# hackeeg-connector-24.net
KiCad netlist of a schematic drawn in EAGLE
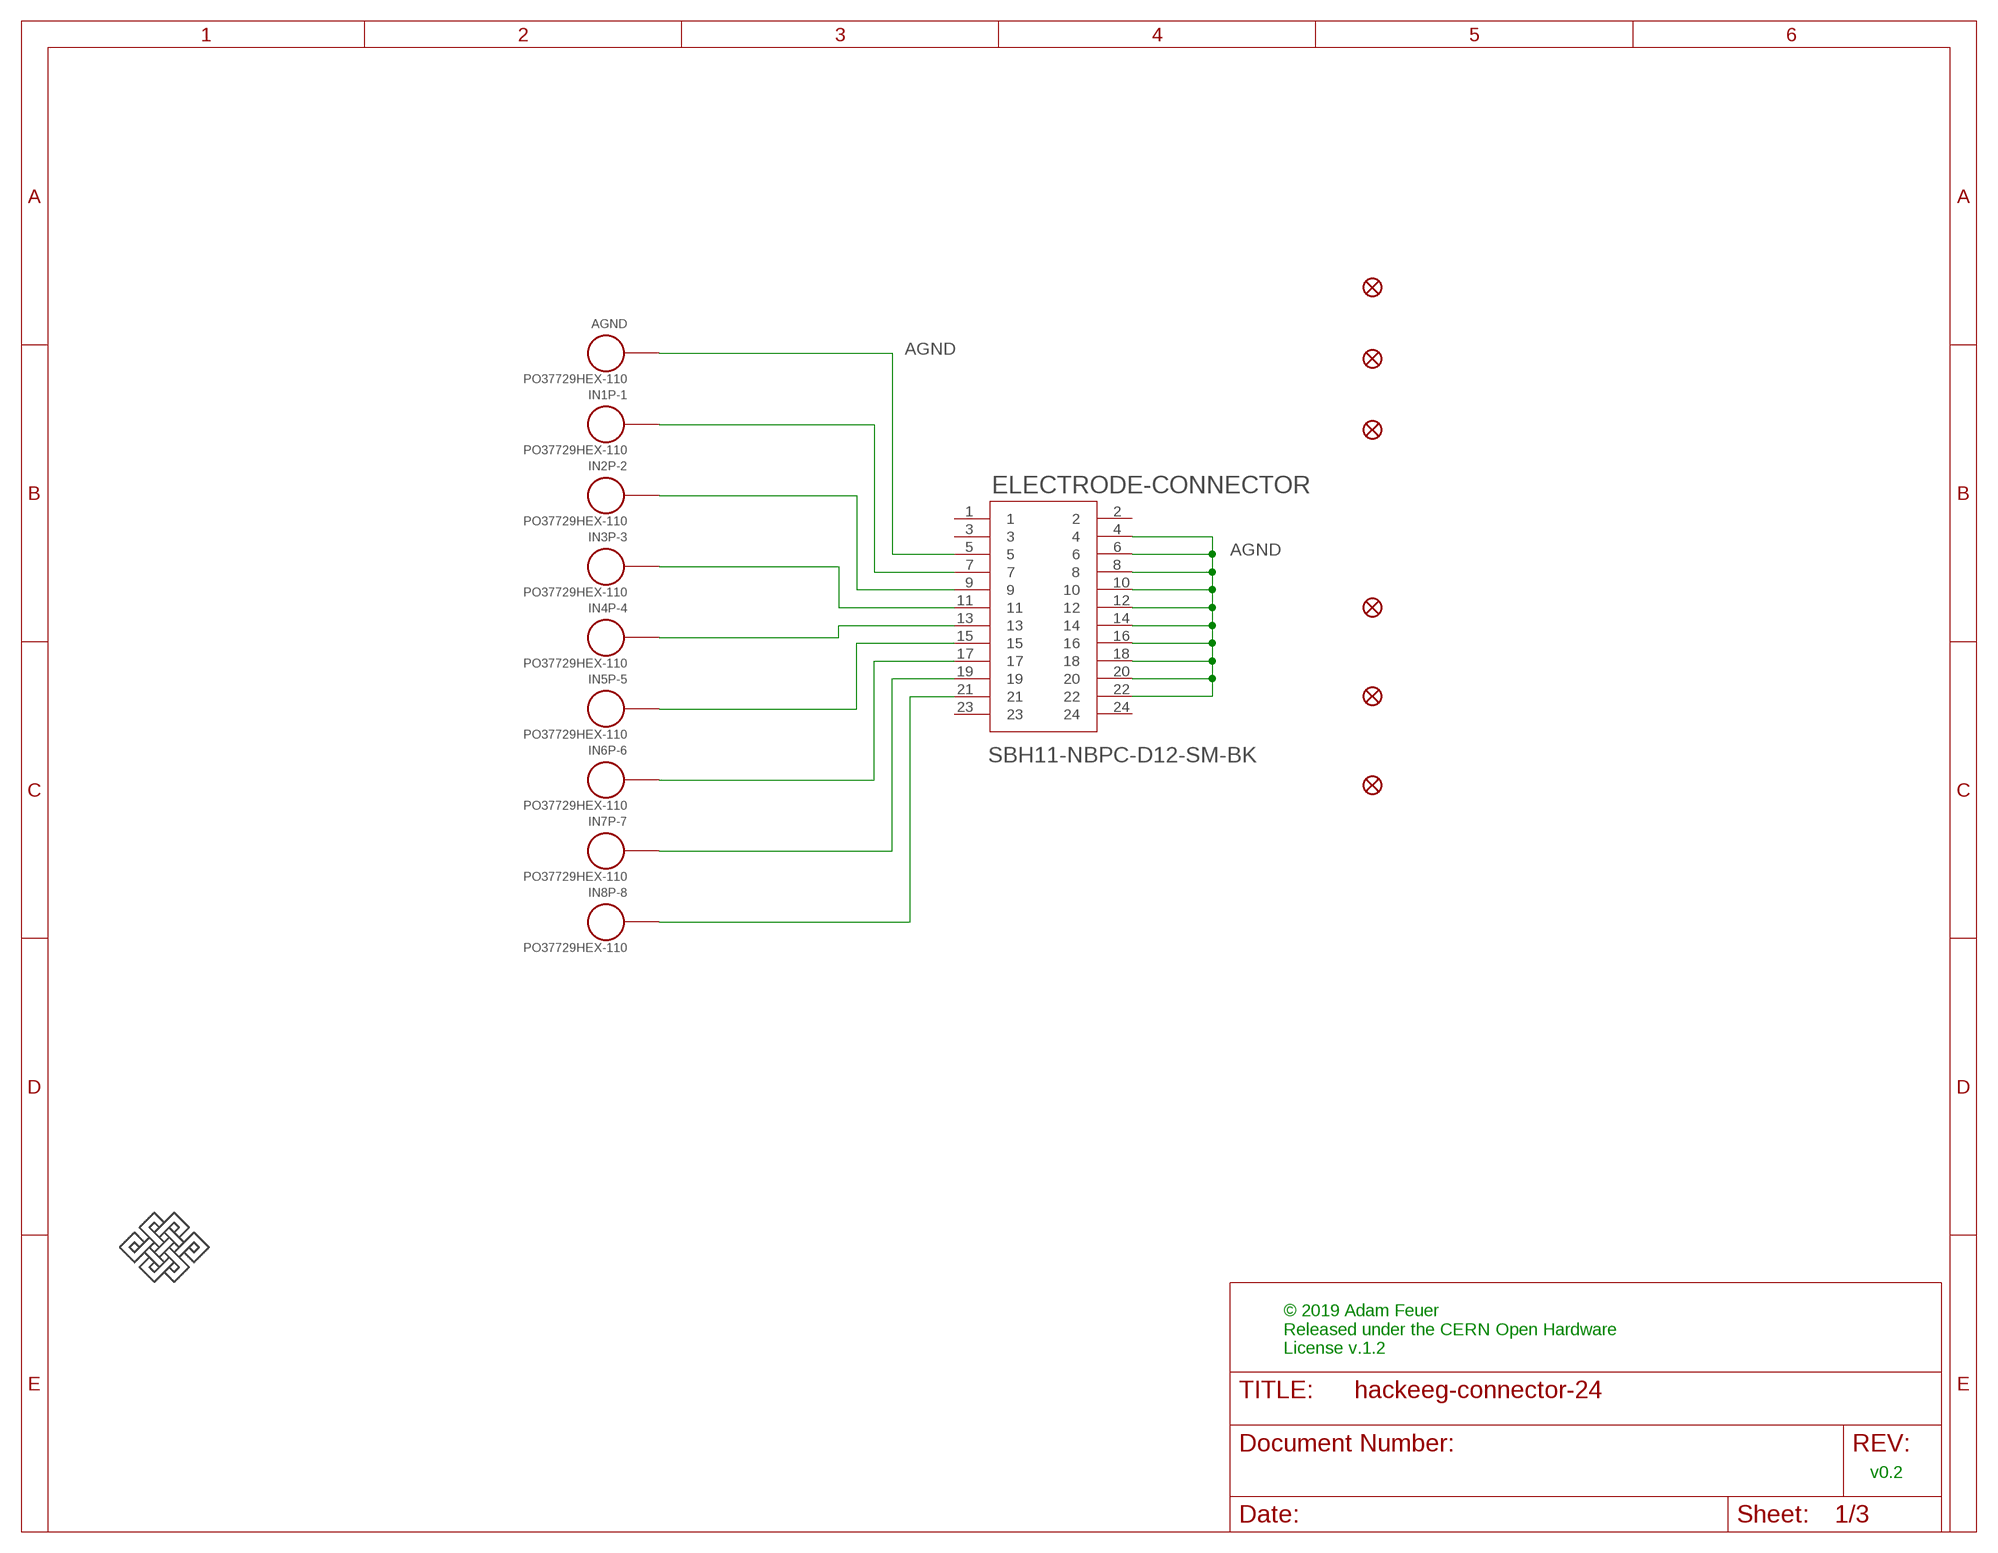
[diagram p0: schematic, sheet 1]
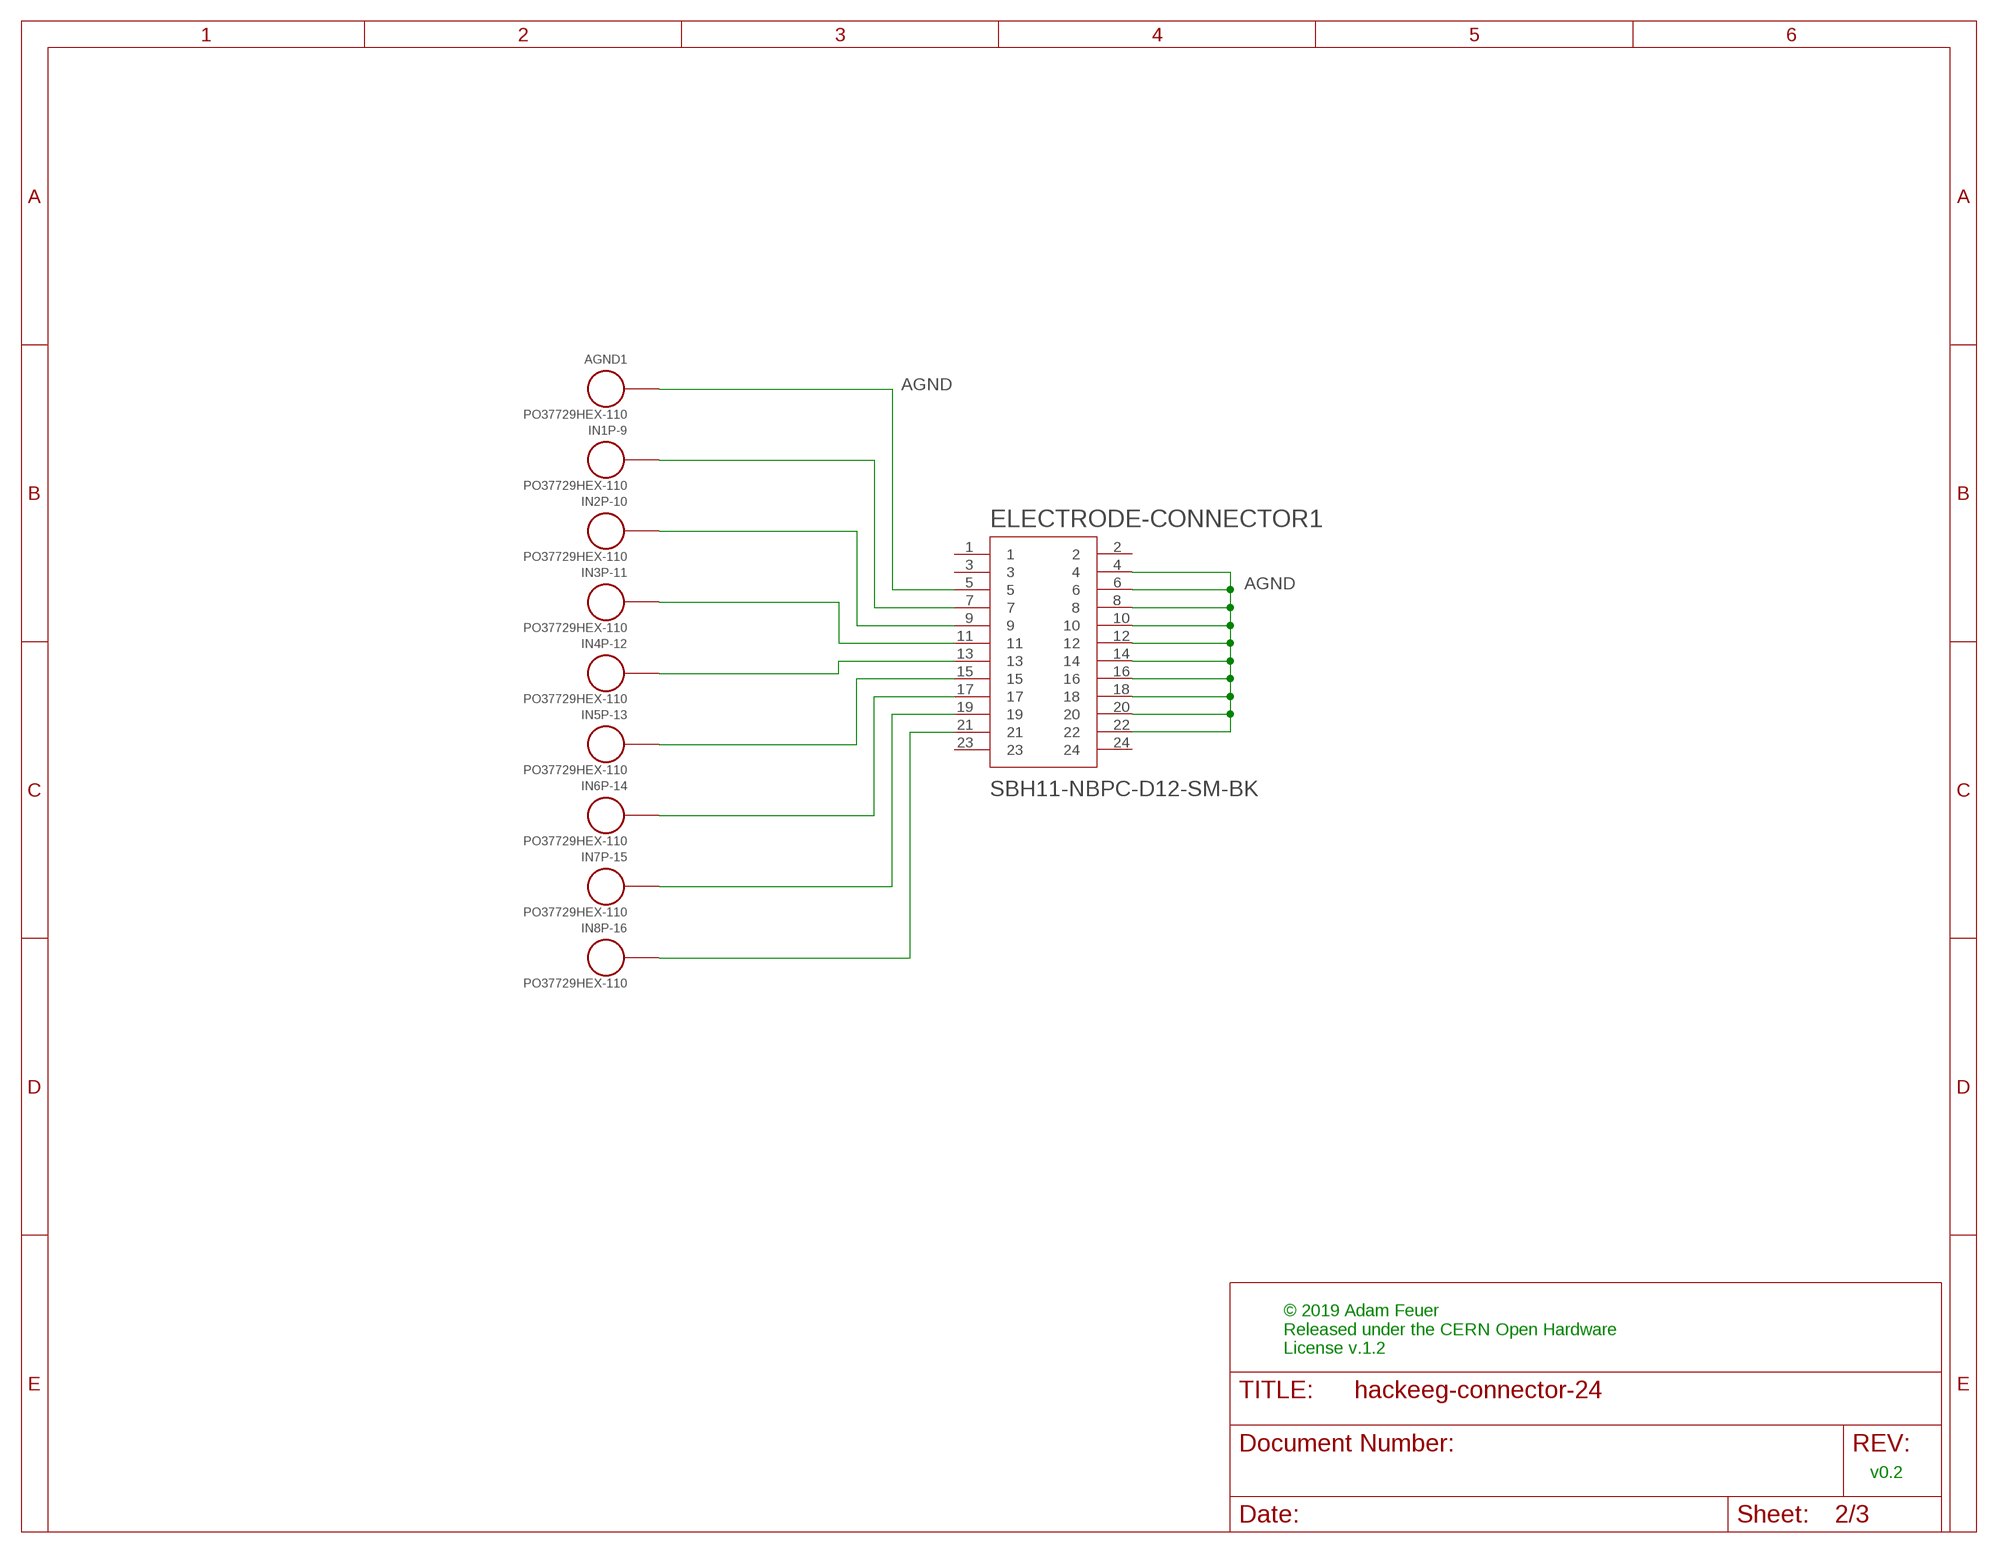
[diagram p1: schematic, sheet 2]
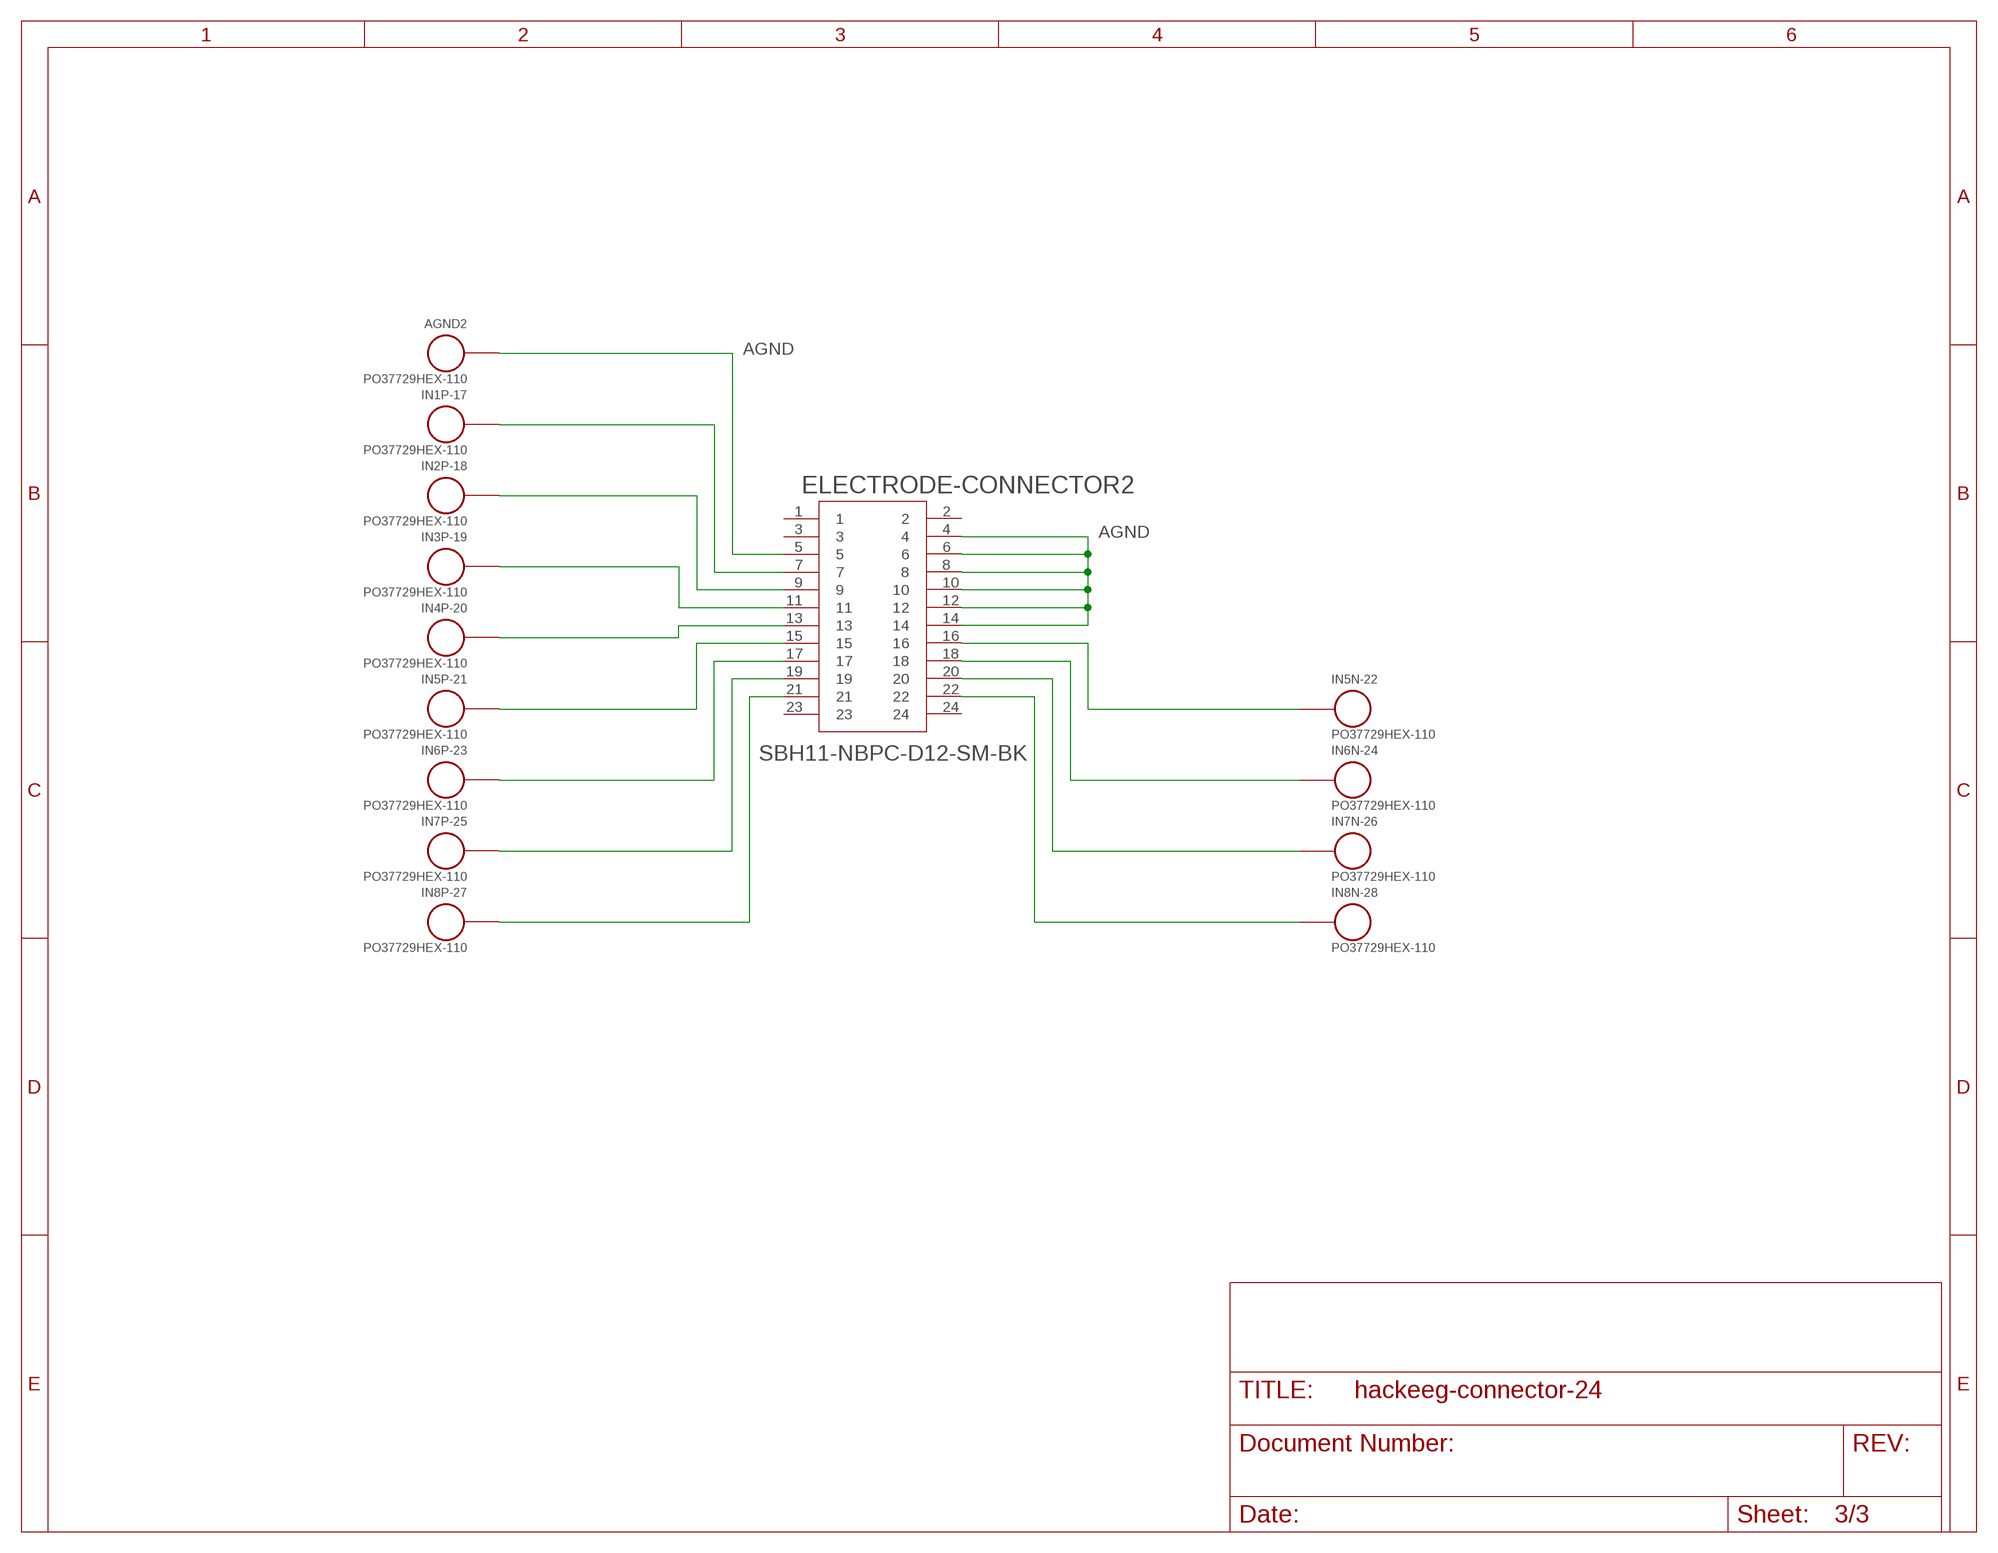
[diagram p2: schematic, sheet 3]

(export (version "E")
  (design (tool "Eeschema 10.0.6"))
  (components
    (comp (ref "AGND2")
      (value "PO37729HEX-110")
      (footprint "eagle-import:HEX-110")
      (libsource (lib "eagle-import") (part "PO37729HEX-110"))
    )
    (comp (ref "ELECTRODE-CONNECTOR2")
      (value "SBH11-NBPC-D12-SM-BK")
      (footprint "eagle-import:SULLINS_SBH11-NBPC-D12-SM-BK")
      (fields (field (name "MF") "Sullins Connector"))
      (libsource (lib "eagle-import") (part "SBH11-NBPC-D12-SM-BK"))
    )
    (comp (ref "IN1P-17")
      (value "PO37729HEX-110")
      (footprint "eagle-import:HEX-110")
      (libsource (lib "eagle-import") (part "PO37729HEX-110"))
    )
    (comp (ref "IN2P-18")
      (value "PO37729HEX-110")
      (footprint "eagle-import:HEX-110")
      (libsource (lib "eagle-import") (part "PO37729HEX-110"))
    )
    (comp (ref "IN3P-19")
      (value "PO37729HEX-110")
      (footprint "eagle-import:HEX-110")
      (libsource (lib "eagle-import") (part "PO37729HEX-110"))
    )
    (comp (ref "IN4P-20")
      (value "PO37729HEX-110")
      (footprint "eagle-import:HEX-110")
      (libsource (lib "eagle-import") (part "PO37729HEX-110"))
    )
    (comp (ref "IN5N-22")
      (value "PO37729HEX-110")
      (footprint "eagle-import:HEX-110")
      (libsource (lib "eagle-import") (part "PO37729HEX-110"))
    )
    (comp (ref "IN5P-21")
      (value "PO37729HEX-110")
      (footprint "eagle-import:HEX-110")
      (libsource (lib "eagle-import") (part "PO37729HEX-110"))
    )
    (comp (ref "IN6N-24")
      (value "PO37729HEX-110")
      (footprint "eagle-import:HEX-110")
      (libsource (lib "eagle-import") (part "PO37729HEX-110"))
    )
    (comp (ref "IN6P-23")
      (value "PO37729HEX-110")
      (footprint "eagle-import:HEX-110")
      (libsource (lib "eagle-import") (part "PO37729HEX-110"))
    )
    (comp (ref "IN7N-26")
      (value "PO37729HEX-110")
      (footprint "eagle-import:HEX-110")
      (libsource (lib "eagle-import") (part "PO37729HEX-110"))
    )
    (comp (ref "IN7P-25")
      (value "PO37729HEX-110")
      (footprint "eagle-import:HEX-110")
      (libsource (lib "eagle-import") (part "PO37729HEX-110"))
    )
    (comp (ref "IN8N-28")
      (value "PO37729HEX-110")
      (footprint "eagle-import:HEX-110")
      (libsource (lib "eagle-import") (part "PO37729HEX-110"))
    )
    (comp (ref "IN8P-27")
      (value "PO37729HEX-110")
      (footprint "eagle-import:HEX-110")
      (libsource (lib "eagle-import") (part "PO37729HEX-110"))
    )
    (comp (ref "AGND")
      (value "PO37729HEX-110")
      (footprint "eagle-import:HEX-110")
      (libsource (lib "eagle-import") (part "PO37729HEX-110"))
    )
    (comp (ref "ELECTRODE-CONNECTOR")
      (value "SBH11-NBPC-D12-SM-BK")
      (footprint "eagle-import:SULLINS_SBH11-NBPC-D12-SM-BK")
      (fields (field (name "MF") "Sullins Connector"))
      (libsource (lib "eagle-import") (part "SBH11-NBPC-D12-SM-BK"))
    )
    (comp (ref "FD1")
      (value "FIDUCIAL1X2")
      (footprint "eagle-import:FIDUCIAL-1X2")
      (libsource (lib "eagle-import") (part "FIDUCIAL1X2"))
    )
    (comp (ref "FD2")
      (value "FIDUCIAL1X2")
      (footprint "eagle-import:FIDUCIAL-1X2")
      (libsource (lib "eagle-import") (part "FIDUCIAL1X2"))
    )
    (comp (ref "FD3")
      (value "FIDUCIAL1X2")
      (footprint "eagle-import:FIDUCIAL-1X2")
      (libsource (lib "eagle-import") (part "FIDUCIAL1X2"))
    )
    (comp (ref "FD4")
      (value "FIDUCIAL1X2")
      (footprint "eagle-import:FIDUCIAL-1X2")
      (libsource (lib "eagle-import") (part "FIDUCIAL1X2"))
    )
    (comp (ref "FD5")
      (value "FIDUCIAL1X2")
      (footprint "eagle-import:FIDUCIAL-1X2")
      (libsource (lib "eagle-import") (part "FIDUCIAL1X2"))
    )
    (comp (ref "FD6")
      (value "FIDUCIAL1X2")
      (footprint "eagle-import:FIDUCIAL-1X2")
      (libsource (lib "eagle-import") (part "FIDUCIAL1X2"))
    )
    (comp (ref "IN1P-1")
      (value "PO37729HEX-110")
      (footprint "eagle-import:HEX-110")
      (libsource (lib "eagle-import") (part "PO37729HEX-110"))
    )
    (comp (ref "IN2P-2")
      (value "PO37729HEX-110")
      (footprint "eagle-import:HEX-110")
      (libsource (lib "eagle-import") (part "PO37729HEX-110"))
    )
    (comp (ref "IN3P-3")
      (value "PO37729HEX-110")
      (footprint "eagle-import:HEX-110")
      (libsource (lib "eagle-import") (part "PO37729HEX-110"))
    )
    (comp (ref "IN4P-4")
      (value "PO37729HEX-110")
      (footprint "eagle-import:HEX-110")
      (libsource (lib "eagle-import") (part "PO37729HEX-110"))
    )
    (comp (ref "IN5P-5")
      (value "PO37729HEX-110")
      (footprint "eagle-import:HEX-110")
      (libsource (lib "eagle-import") (part "PO37729HEX-110"))
    )
    (comp (ref "IN6P-6")
      (value "PO37729HEX-110")
      (footprint "eagle-import:HEX-110")
      (libsource (lib "eagle-import") (part "PO37729HEX-110"))
    )
    (comp (ref "IN7P-7")
      (value "PO37729HEX-110")
      (footprint "eagle-import:HEX-110")
      (libsource (lib "eagle-import") (part "PO37729HEX-110"))
    )
    (comp (ref "IN8P-8")
      (value "PO37729HEX-110")
      (footprint "eagle-import:HEX-110")
      (libsource (lib "eagle-import") (part "PO37729HEX-110"))
    )
    (comp (ref "U$1")
      (value "ENDLESSKNOTENDLESSKNOT-MEDIUM")
      (footprint "eagle-import:ENDLESSKNOT-MEDIUM")
      (libsource (lib "eagle-import") (part "ENDLESSKNOTENDLESSKNOT-MEDIUM"))
    )
    (comp (ref "AGND1")
      (value "PO37729HEX-110")
      (footprint "eagle-import:HEX-110")
      (libsource (lib "eagle-import") (part "PO37729HEX-110"))
    )
    (comp (ref "ELECTRODE-CONNECTOR1")
      (value "SBH11-NBPC-D12-SM-BK")
      (footprint "eagle-import:SULLINS_SBH11-NBPC-D12-SM-BK")
      (fields (field (name "MF") "Sullins Connector"))
      (libsource (lib "eagle-import") (part "SBH11-NBPC-D12-SM-BK"))
    )
    (comp (ref "IN1P-9")
      (value "PO37729HEX-110")
      (footprint "eagle-import:HEX-110")
      (libsource (lib "eagle-import") (part "PO37729HEX-110"))
    )
    (comp (ref "IN2P-10")
      (value "PO37729HEX-110")
      (footprint "eagle-import:HEX-110")
      (libsource (lib "eagle-import") (part "PO37729HEX-110"))
    )
    (comp (ref "IN3P-11")
      (value "PO37729HEX-110")
      (footprint "eagle-import:HEX-110")
      (libsource (lib "eagle-import") (part "PO37729HEX-110"))
    )
    (comp (ref "IN4P-12")
      (value "PO37729HEX-110")
      (footprint "eagle-import:HEX-110")
      (libsource (lib "eagle-import") (part "PO37729HEX-110"))
    )
    (comp (ref "IN5P-13")
      (value "PO37729HEX-110")
      (footprint "eagle-import:HEX-110")
      (libsource (lib "eagle-import") (part "PO37729HEX-110"))
    )
    (comp (ref "IN6P-14")
      (value "PO37729HEX-110")
      (footprint "eagle-import:HEX-110")
      (libsource (lib "eagle-import") (part "PO37729HEX-110"))
    )
    (comp (ref "IN7P-15")
      (value "PO37729HEX-110")
      (footprint "eagle-import:HEX-110")
      (libsource (lib "eagle-import") (part "PO37729HEX-110"))
    )
    (comp (ref "IN8P-16")
      (value "PO37729HEX-110")
      (footprint "eagle-import:HEX-110")
      (libsource (lib "eagle-import") (part "PO37729HEX-110"))
    )
  )
  (nets
    (net (code "1") (name "AGND") (class "Default")
      (node (ref "AGND") (pin "SIGNAL") (pinfunction "SIGNAL_SIGNAL") (pintype "bidirectional"))
      (node (ref "AGND1") (pin "SIGNAL") (pinfunction "SIGNAL_SIGNAL") (pintype "bidirectional"))
      (node (ref "AGND2") (pin "SIGNAL") (pinfunction "SIGNAL_SIGNAL") (pintype "bidirectional"))
      (node (ref "ELECTRODE-CONNECTOR") (pin "10") (pinfunction "10_10") (pintype "passive"))
      (node (ref "ELECTRODE-CONNECTOR") (pin "12") (pinfunction "12_12") (pintype "passive"))
      (node (ref "ELECTRODE-CONNECTOR") (pin "14") (pinfunction "14_14") (pintype "passive"))
      (node (ref "ELECTRODE-CONNECTOR") (pin "16") (pinfunction "16_16") (pintype "passive"))
      (node (ref "ELECTRODE-CONNECTOR") (pin "18") (pinfunction "18_18") (pintype "passive"))
      (node (ref "ELECTRODE-CONNECTOR") (pin "20") (pinfunction "20_20") (pintype "passive"))
      (node (ref "ELECTRODE-CONNECTOR") (pin "22") (pinfunction "22_22") (pintype "passive"))
      (node (ref "ELECTRODE-CONNECTOR") (pin "4") (pinfunction "4_4") (pintype "passive"))
      (node (ref "ELECTRODE-CONNECTOR") (pin "5") (pinfunction "5_5") (pintype "passive"))
      (node (ref "ELECTRODE-CONNECTOR") (pin "6") (pinfunction "6_6") (pintype "passive"))
      (node (ref "ELECTRODE-CONNECTOR") (pin "8") (pinfunction "8_8") (pintype "passive"))
      (node (ref "ELECTRODE-CONNECTOR1") (pin "10") (pinfunction "10_10") (pintype "passive"))
      (node (ref "ELECTRODE-CONNECTOR1") (pin "12") (pinfunction "12_12") (pintype "passive"))
      (node (ref "ELECTRODE-CONNECTOR1") (pin "14") (pinfunction "14_14") (pintype "passive"))
      (node (ref "ELECTRODE-CONNECTOR1") (pin "16") (pinfunction "16_16") (pintype "passive"))
      (node (ref "ELECTRODE-CONNECTOR1") (pin "18") (pinfunction "18_18") (pintype "passive"))
      (node (ref "ELECTRODE-CONNECTOR1") (pin "20") (pinfunction "20_20") (pintype "passive"))
      (node (ref "ELECTRODE-CONNECTOR1") (pin "22") (pinfunction "22_22") (pintype "passive"))
      (node (ref "ELECTRODE-CONNECTOR1") (pin "4") (pinfunction "4_4") (pintype "passive"))
      (node (ref "ELECTRODE-CONNECTOR1") (pin "5") (pinfunction "5_5") (pintype "passive"))
      (node (ref "ELECTRODE-CONNECTOR1") (pin "6") (pinfunction "6_6") (pintype "passive"))
      (node (ref "ELECTRODE-CONNECTOR1") (pin "8") (pinfunction "8_8") (pintype "passive"))
      (node (ref "ELECTRODE-CONNECTOR2") (pin "10") (pinfunction "10_10") (pintype "passive"))
      (node (ref "ELECTRODE-CONNECTOR2") (pin "12") (pinfunction "12_12") (pintype "passive"))
      (node (ref "ELECTRODE-CONNECTOR2") (pin "14") (pinfunction "14_14") (pintype "passive"))
      (node (ref "ELECTRODE-CONNECTOR2") (pin "4") (pinfunction "4_4") (pintype "passive"))
      (node (ref "ELECTRODE-CONNECTOR2") (pin "5") (pinfunction "5_5") (pintype "passive"))
      (node (ref "ELECTRODE-CONNECTOR2") (pin "6") (pinfunction "6_6") (pintype "passive"))
      (node (ref "ELECTRODE-CONNECTOR2") (pin "8") (pinfunction "8_8") (pintype "passive"))
    )
    (net (code "2") (name "Net-(ELECTRODE-CONNECTOR-Pad7)") (class "Default")
      (node (ref "ELECTRODE-CONNECTOR") (pin "7") (pinfunction "7_7") (pintype "passive"))
      (node (ref "IN1P-1") (pin "SIGNAL") (pinfunction "SIGNAL_SIGNAL") (pintype "bidirectional"))
    )
    (net (code "3") (name "Net-(ELECTRODE-CONNECTOR-Pad9)") (class "Default")
      (node (ref "ELECTRODE-CONNECTOR") (pin "9") (pinfunction "9_9") (pintype "passive"))
      (node (ref "IN2P-2") (pin "SIGNAL") (pinfunction "SIGNAL_SIGNAL") (pintype "bidirectional"))
    )
    (net (code "4") (name "Net-(ELECTRODE-CONNECTOR-Pad11)") (class "Default")
      (node (ref "ELECTRODE-CONNECTOR") (pin "11") (pinfunction "11_11") (pintype "passive"))
      (node (ref "IN3P-3") (pin "SIGNAL") (pinfunction "SIGNAL_SIGNAL") (pintype "bidirectional"))
    )
    (net (code "5") (name "Net-(ELECTRODE-CONNECTOR-Pad13)") (class "Default")
      (node (ref "ELECTRODE-CONNECTOR") (pin "13") (pinfunction "13_13") (pintype "passive"))
      (node (ref "IN4P-4") (pin "SIGNAL") (pinfunction "SIGNAL_SIGNAL") (pintype "bidirectional"))
    )
    (net (code "6") (name "Net-(ELECTRODE-CONNECTOR-Pad15)") (class "Default")
      (node (ref "ELECTRODE-CONNECTOR") (pin "15") (pinfunction "15_15") (pintype "passive"))
      (node (ref "IN5P-5") (pin "SIGNAL") (pinfunction "SIGNAL_SIGNAL") (pintype "bidirectional"))
    )
    (net (code "7") (name "Net-(ELECTRODE-CONNECTOR-Pad17)") (class "Default")
      (node (ref "ELECTRODE-CONNECTOR") (pin "17") (pinfunction "17_17") (pintype "passive"))
      (node (ref "IN6P-6") (pin "SIGNAL") (pinfunction "SIGNAL_SIGNAL") (pintype "bidirectional"))
    )
    (net (code "8") (name "Net-(ELECTRODE-CONNECTOR-Pad19)") (class "Default")
      (node (ref "ELECTRODE-CONNECTOR") (pin "19") (pinfunction "19_19") (pintype "passive"))
      (node (ref "IN7P-7") (pin "SIGNAL") (pinfunction "SIGNAL_SIGNAL") (pintype "bidirectional"))
    )
    (net (code "9") (name "Net-(ELECTRODE-CONNECTOR-Pad21)") (class "Default")
      (node (ref "ELECTRODE-CONNECTOR") (pin "21") (pinfunction "21_21") (pintype "passive"))
      (node (ref "IN8P-8") (pin "SIGNAL") (pinfunction "SIGNAL_SIGNAL") (pintype "bidirectional"))
    )
    (net (code "10") (name "Net-(ELECTRODE-CONNECTOR1-Pad7)") (class "Default")
      (node (ref "ELECTRODE-CONNECTOR1") (pin "7") (pinfunction "7_7") (pintype "passive"))
      (node (ref "IN1P-9") (pin "SIGNAL") (pinfunction "SIGNAL_SIGNAL") (pintype "bidirectional"))
    )
    (net (code "11") (name "Net-(ELECTRODE-CONNECTOR1-Pad9)") (class "Default")
      (node (ref "ELECTRODE-CONNECTOR1") (pin "9") (pinfunction "9_9") (pintype "passive"))
      (node (ref "IN2P-10") (pin "SIGNAL") (pinfunction "SIGNAL_SIGNAL") (pintype "bidirectional"))
    )
    (net (code "12") (name "Net-(ELECTRODE-CONNECTOR1-Pad11)") (class "Default")
      (node (ref "ELECTRODE-CONNECTOR1") (pin "11") (pinfunction "11_11") (pintype "passive"))
      (node (ref "IN3P-11") (pin "SIGNAL") (pinfunction "SIGNAL_SIGNAL") (pintype "bidirectional"))
    )
    (net (code "13") (name "Net-(ELECTRODE-CONNECTOR1-Pad13)") (class "Default")
      (node (ref "ELECTRODE-CONNECTOR1") (pin "13") (pinfunction "13_13") (pintype "passive"))
      (node (ref "IN4P-12") (pin "SIGNAL") (pinfunction "SIGNAL_SIGNAL") (pintype "bidirectional"))
    )
    (net (code "14") (name "Net-(ELECTRODE-CONNECTOR1-Pad15)") (class "Default")
      (node (ref "ELECTRODE-CONNECTOR1") (pin "15") (pinfunction "15_15") (pintype "passive"))
      (node (ref "IN5P-13") (pin "SIGNAL") (pinfunction "SIGNAL_SIGNAL") (pintype "bidirectional"))
    )
    (net (code "15") (name "Net-(ELECTRODE-CONNECTOR1-Pad17)") (class "Default")
      (node (ref "ELECTRODE-CONNECTOR1") (pin "17") (pinfunction "17_17") (pintype "passive"))
      (node (ref "IN6P-14") (pin "SIGNAL") (pinfunction "SIGNAL_SIGNAL") (pintype "bidirectional"))
    )
    (net (code "16") (name "Net-(ELECTRODE-CONNECTOR1-Pad19)") (class "Default")
      (node (ref "ELECTRODE-CONNECTOR1") (pin "19") (pinfunction "19_19") (pintype "passive"))
      (node (ref "IN7P-15") (pin "SIGNAL") (pinfunction "SIGNAL_SIGNAL") (pintype "bidirectional"))
    )
    (net (code "17") (name "Net-(ELECTRODE-CONNECTOR1-Pad21)") (class "Default")
      (node (ref "ELECTRODE-CONNECTOR1") (pin "21") (pinfunction "21_21") (pintype "passive"))
      (node (ref "IN8P-16") (pin "SIGNAL") (pinfunction "SIGNAL_SIGNAL") (pintype "bidirectional"))
    )
    (net (code "18") (name "Net-(ELECTRODE-CONNECTOR2-Pad7)") (class "Default")
      (node (ref "ELECTRODE-CONNECTOR2") (pin "7") (pinfunction "7_7") (pintype "passive"))
      (node (ref "IN1P-17") (pin "SIGNAL") (pinfunction "SIGNAL_SIGNAL") (pintype "bidirectional"))
    )
    (net (code "19") (name "Net-(ELECTRODE-CONNECTOR2-Pad9)") (class "Default")
      (node (ref "ELECTRODE-CONNECTOR2") (pin "9") (pinfunction "9_9") (pintype "passive"))
      (node (ref "IN2P-18") (pin "SIGNAL") (pinfunction "SIGNAL_SIGNAL") (pintype "bidirectional"))
    )
    (net (code "20") (name "Net-(ELECTRODE-CONNECTOR2-Pad11)") (class "Default")
      (node (ref "ELECTRODE-CONNECTOR2") (pin "11") (pinfunction "11_11") (pintype "passive"))
      (node (ref "IN3P-19") (pin "SIGNAL") (pinfunction "SIGNAL_SIGNAL") (pintype "bidirectional"))
    )
    (net (code "21") (name "Net-(ELECTRODE-CONNECTOR2-Pad13)") (class "Default")
      (node (ref "ELECTRODE-CONNECTOR2") (pin "13") (pinfunction "13_13") (pintype "passive"))
      (node (ref "IN4P-20") (pin "SIGNAL") (pinfunction "SIGNAL_SIGNAL") (pintype "bidirectional"))
    )
    (net (code "22") (name "Net-(ELECTRODE-CONNECTOR2-Pad15)") (class "Default")
      (node (ref "ELECTRODE-CONNECTOR2") (pin "15") (pinfunction "15_15") (pintype "passive"))
      (node (ref "IN5P-21") (pin "SIGNAL") (pinfunction "SIGNAL_SIGNAL") (pintype "bidirectional"))
    )
    (net (code "23") (name "Net-(ELECTRODE-CONNECTOR2-Pad16)") (class "Default")
      (node (ref "ELECTRODE-CONNECTOR2") (pin "16") (pinfunction "16_16") (pintype "passive"))
      (node (ref "IN5N-22") (pin "SIGNAL") (pinfunction "SIGNAL_SIGNAL") (pintype "bidirectional"))
    )
    (net (code "24") (name "Net-(ELECTRODE-CONNECTOR2-Pad17)") (class "Default")
      (node (ref "ELECTRODE-CONNECTOR2") (pin "17") (pinfunction "17_17") (pintype "passive"))
      (node (ref "IN6P-23") (pin "SIGNAL") (pinfunction "SIGNAL_SIGNAL") (pintype "bidirectional"))
    )
    (net (code "25") (name "Net-(ELECTRODE-CONNECTOR2-Pad18)") (class "Default")
      (node (ref "ELECTRODE-CONNECTOR2") (pin "18") (pinfunction "18_18") (pintype "passive"))
      (node (ref "IN6N-24") (pin "SIGNAL") (pinfunction "SIGNAL_SIGNAL") (pintype "bidirectional"))
    )
    (net (code "26") (name "Net-(ELECTRODE-CONNECTOR2-Pad19)") (class "Default")
      (node (ref "ELECTRODE-CONNECTOR2") (pin "19") (pinfunction "19_19") (pintype "passive"))
      (node (ref "IN7P-25") (pin "SIGNAL") (pinfunction "SIGNAL_SIGNAL") (pintype "bidirectional"))
    )
    (net (code "27") (name "Net-(ELECTRODE-CONNECTOR2-Pad20)") (class "Default")
      (node (ref "ELECTRODE-CONNECTOR2") (pin "20") (pinfunction "20_20") (pintype "passive"))
      (node (ref "IN7N-26") (pin "SIGNAL") (pinfunction "SIGNAL_SIGNAL") (pintype "bidirectional"))
    )
    (net (code "28") (name "Net-(ELECTRODE-CONNECTOR2-Pad21)") (class "Default")
      (node (ref "ELECTRODE-CONNECTOR2") (pin "21") (pinfunction "21_21") (pintype "passive"))
      (node (ref "IN8P-27") (pin "SIGNAL") (pinfunction "SIGNAL_SIGNAL") (pintype "bidirectional"))
    )
    (net (code "29") (name "Net-(ELECTRODE-CONNECTOR2-Pad22)") (class "Default")
      (node (ref "ELECTRODE-CONNECTOR2") (pin "22") (pinfunction "22_22") (pintype "passive"))
      (node (ref "IN8N-28") (pin "SIGNAL") (pinfunction "SIGNAL_SIGNAL") (pintype "bidirectional"))
    )
    (net (code "30") (name "unconnected-(ELECTRODE-CONNECTOR-Pad1)") (class "Default")
      (node (ref "ELECTRODE-CONNECTOR") (pin "1") (pinfunction "1_1") (pintype "passive"))
    )
    (net (code "31") (name "unconnected-(ELECTRODE-CONNECTOR-Pad2)") (class "Default")
      (node (ref "ELECTRODE-CONNECTOR") (pin "2") (pinfunction "2_2") (pintype "passive"))
    )
    (net (code "32") (name "unconnected-(ELECTRODE-CONNECTOR-Pad3)") (class "Default")
      (node (ref "ELECTRODE-CONNECTOR") (pin "3") (pinfunction "3_3") (pintype "passive"))
    )
    (net (code "33") (name "unconnected-(ELECTRODE-CONNECTOR-Pad23)") (class "Default")
      (node (ref "ELECTRODE-CONNECTOR") (pin "23") (pinfunction "23_23") (pintype "passive"))
    )
    (net (code "34") (name "unconnected-(ELECTRODE-CONNECTOR-Pad24)") (class "Default")
      (node (ref "ELECTRODE-CONNECTOR") (pin "24") (pinfunction "24_24") (pintype "passive"))
    )
    (net (code "35") (name "unconnected-(ELECTRODE-CONNECTOR1-Pad1)") (class "Default")
      (node (ref "ELECTRODE-CONNECTOR1") (pin "1") (pinfunction "1_1") (pintype "passive"))
    )
    (net (code "36") (name "unconnected-(ELECTRODE-CONNECTOR1-Pad2)") (class "Default")
      (node (ref "ELECTRODE-CONNECTOR1") (pin "2") (pinfunction "2_2") (pintype "passive"))
    )
    (net (code "37") (name "unconnected-(ELECTRODE-CONNECTOR1-Pad3)") (class "Default")
      (node (ref "ELECTRODE-CONNECTOR1") (pin "3") (pinfunction "3_3") (pintype "passive"))
    )
    (net (code "38") (name "unconnected-(ELECTRODE-CONNECTOR1-Pad23)") (class "Default")
      (node (ref "ELECTRODE-CONNECTOR1") (pin "23") (pinfunction "23_23") (pintype "passive"))
    )
    (net (code "39") (name "unconnected-(ELECTRODE-CONNECTOR1-Pad24)") (class "Default")
      (node (ref "ELECTRODE-CONNECTOR1") (pin "24") (pinfunction "24_24") (pintype "passive"))
    )
    (net (code "40") (name "unconnected-(ELECTRODE-CONNECTOR2-Pad1)") (class "Default")
      (node (ref "ELECTRODE-CONNECTOR2") (pin "1") (pinfunction "1_1") (pintype "passive"))
    )
    (net (code "41") (name "unconnected-(ELECTRODE-CONNECTOR2-Pad2)") (class "Default")
      (node (ref "ELECTRODE-CONNECTOR2") (pin "2") (pinfunction "2_2") (pintype "passive"))
    )
    (net (code "42") (name "unconnected-(ELECTRODE-CONNECTOR2-Pad3)") (class "Default")
      (node (ref "ELECTRODE-CONNECTOR2") (pin "3") (pinfunction "3_3") (pintype "passive"))
    )
    (net (code "43") (name "unconnected-(ELECTRODE-CONNECTOR2-Pad23)") (class "Default")
      (node (ref "ELECTRODE-CONNECTOR2") (pin "23") (pinfunction "23_23") (pintype "passive"))
    )
    (net (code "44") (name "unconnected-(ELECTRODE-CONNECTOR2-Pad24)") (class "Default")
      (node (ref "ELECTRODE-CONNECTOR2") (pin "24") (pinfunction "24_24") (pintype "passive"))
    )
  )
)
